# Electrical_Panel.net
KiCad netlist of a schematic drawn in Altium Designer
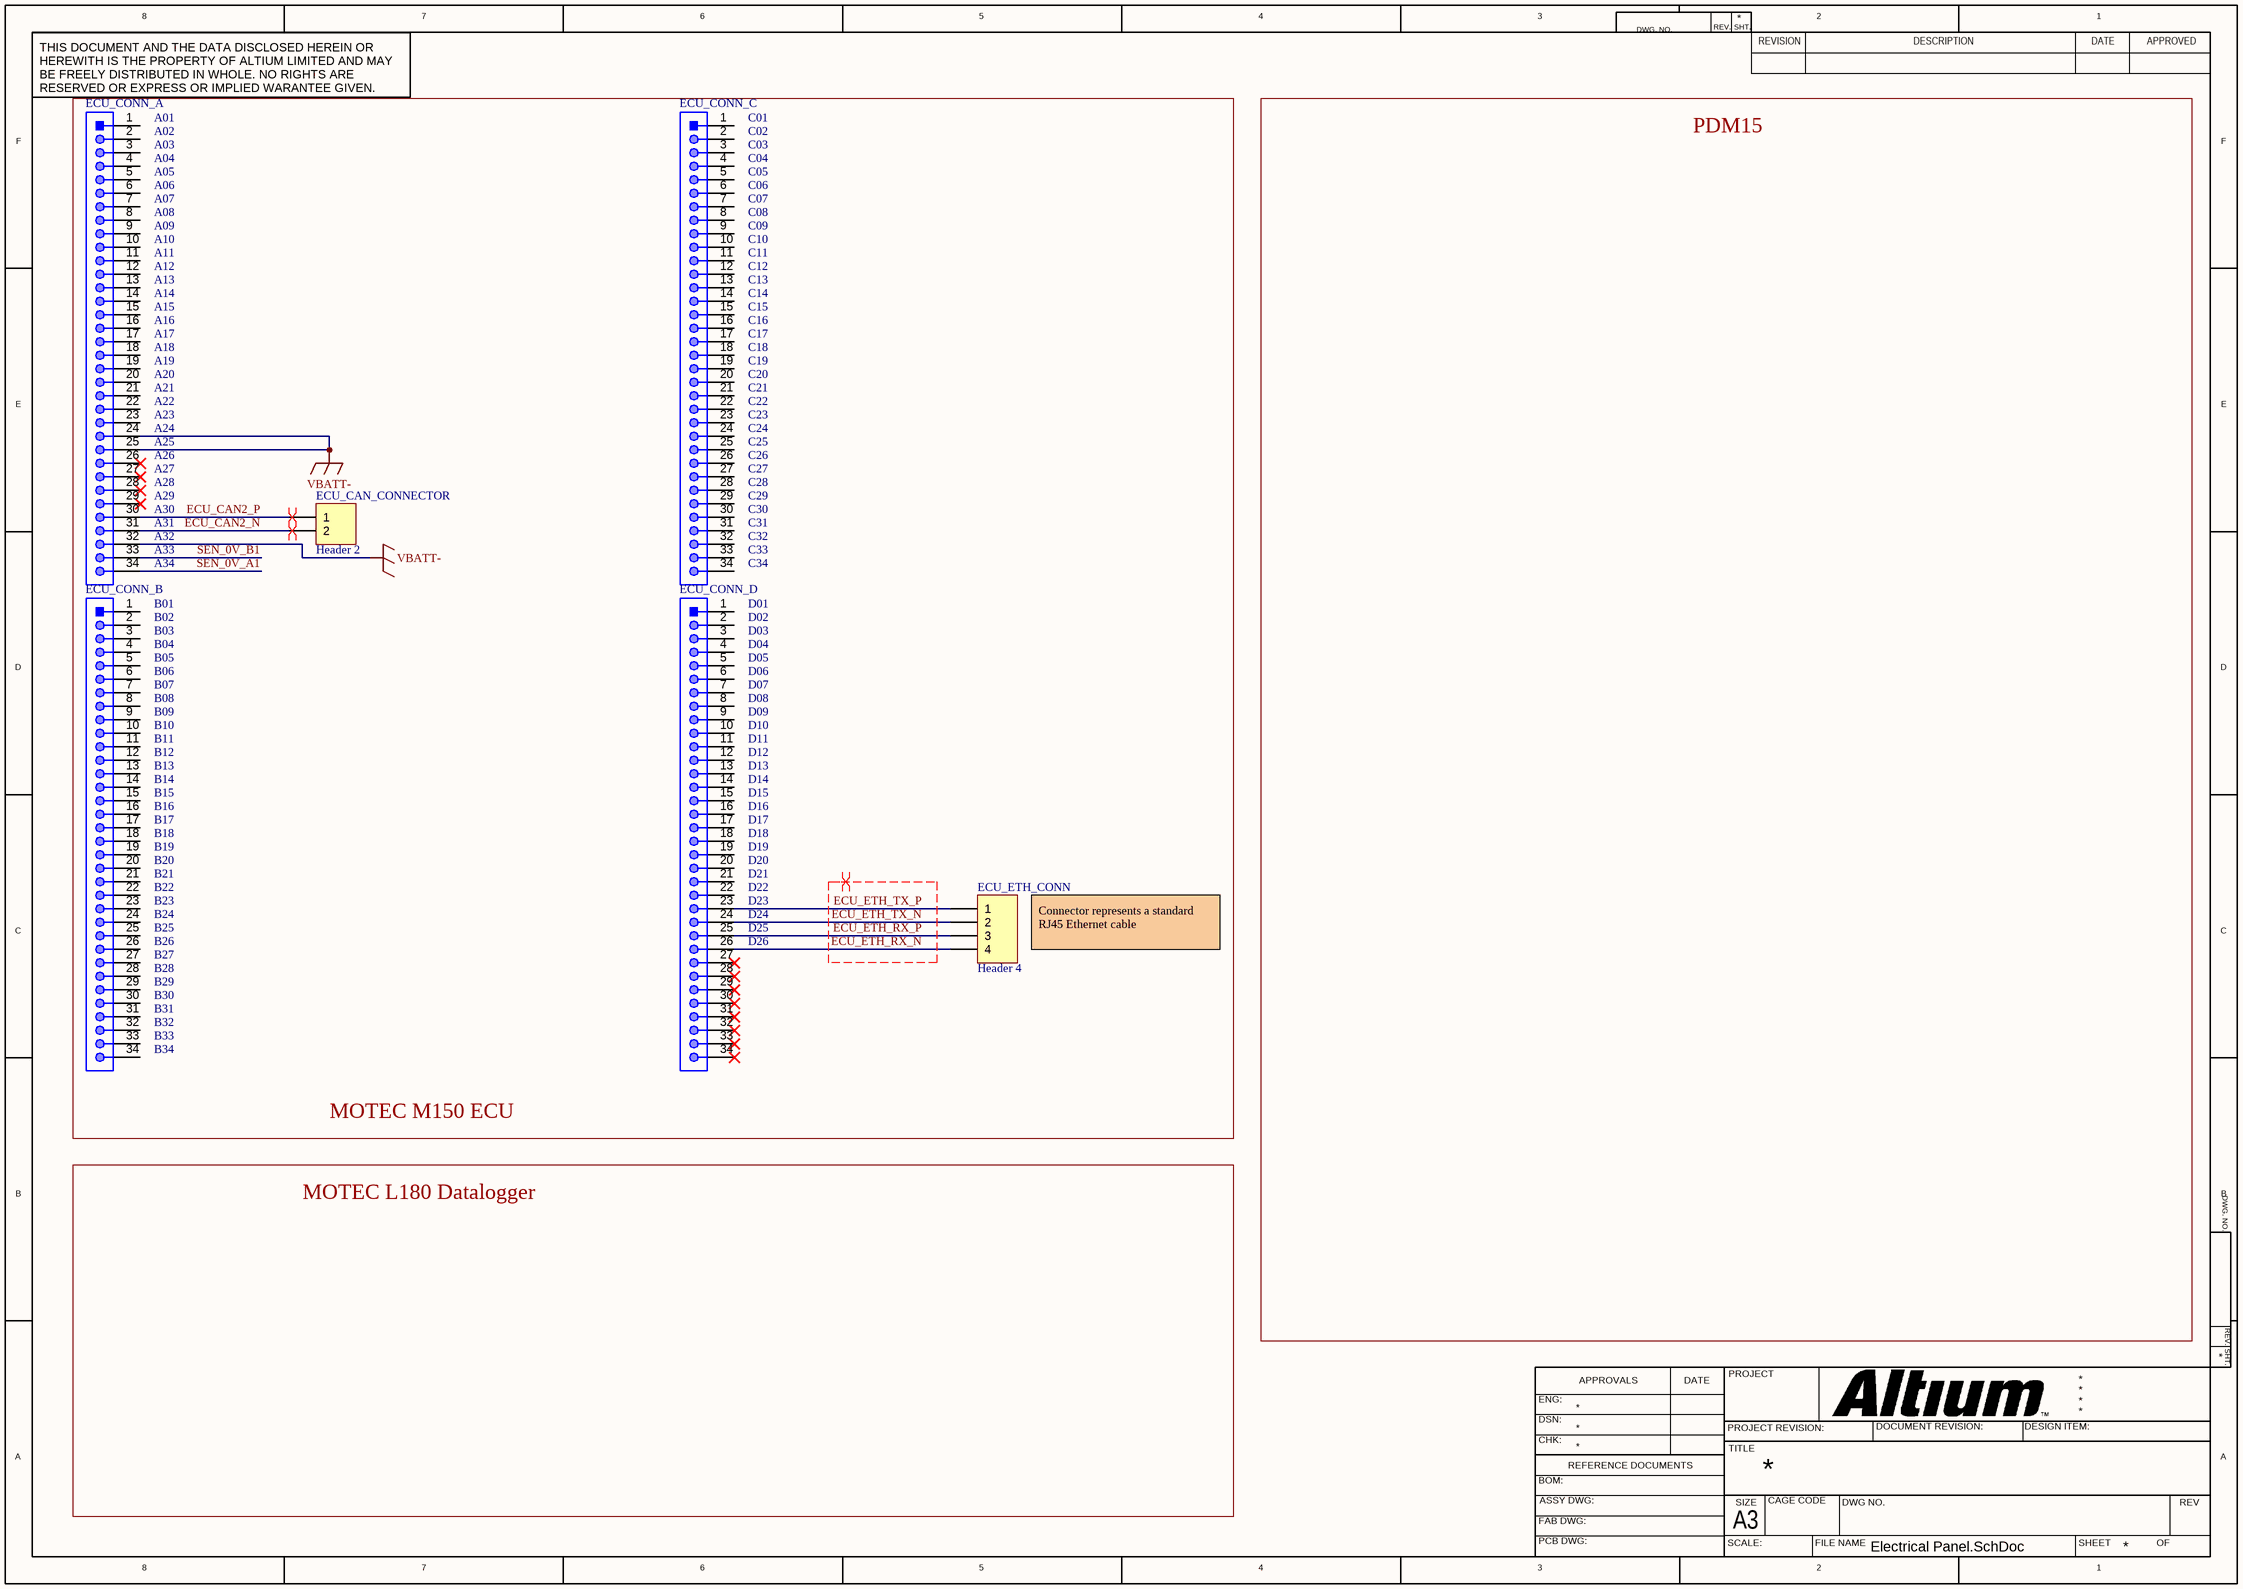
[diagram p0: Electrical Panel.SchDoc]

(export (version "E")
  (design (tool "Eeschema 10.0.6"))
  (components
    (comp (ref "ECU_CAN_CONNECTOR")
      (value "Header 2")
      (footprint "HDR1X2")
      (description "Header, 2-Pin")
      (fields (field (name "PUBLISHER") "Altium Limited"))
      (libsource (lib "Miscellaneous Connectors") (part "Header 2"))
    )
    (comp (ref "ECU_CONN_A")
      (value "61303411021")
      (footprint "61303411021")
      (description "THT Angled Pin Header WR-PHD, Pitch 2.54 mm, Single Row, 34 pins")
      (fields (field (name "MANUFACTURER") "Wurth Elektronik") (field (name "PUBLISHER") "WurthElektronik"))
      (libsource (lib "Altium Content Vault") (part "WE-CN-1P-M-R34"))
    )
    (comp (ref "ECU_CONN_B")
      (value "61303411021")
      (footprint "61303411021")
      (description "THT Angled Pin Header WR-PHD, Pitch 2.54 mm, Single Row, 34 pins")
      (fields (field (name "MANUFACTURER") "Wurth Elektronik") (field (name "PUBLISHER") "WurthElektronik"))
      (libsource (lib "Altium Content Vault") (part "WE-CN-1P-M-R34"))
    )
    (comp (ref "ECU_CONN_C")
      (value "61303411021")
      (footprint "61303411021")
      (description "THT Angled Pin Header WR-PHD, Pitch 2.54 mm, Single Row, 34 pins")
      (fields (field (name "MANUFACTURER") "Wurth Elektronik") (field (name "PUBLISHER") "WurthElektronik"))
      (libsource (lib "Altium Content Vault") (part "WE-CN-1P-M-R34"))
    )
    (comp (ref "ECU_CONN_D")
      (value "61303411021")
      (footprint "61303411021")
      (description "THT Angled Pin Header WR-PHD, Pitch 2.54 mm, Single Row, 34 pins")
      (fields (field (name "MANUFACTURER") "Wurth Elektronik") (field (name "PUBLISHER") "WurthElektronik"))
      (libsource (lib "Altium Content Vault") (part "WE-CN-1P-M-R34"))
    )
    (comp (ref "ECU_ETH_CONN")
      (value "Header 4")
      (footprint "HDR1X4")
      (description "Header, 4-Pin")
      (fields (field (name "PUBLISHER") "Altium Limited"))
      (libsource (lib "Miscellaneous Connectors") (part "Header 4"))
    )
  )
  (nets
    (net (code "1") (name "/ECU_CAN2_N") (class "Default")
      (node (ref "ECU_CAN_CONNECTOR") (pin "2") (pinfunction "2_2") (pintype "passive"))
      (node (ref "ECU_CONN_A") (pin "31") (pinfunction "31_31") (pintype "passive"))
    )
    (net (code "2") (name "/ECU_CAN2_P") (class "Default")
      (node (ref "ECU_CAN_CONNECTOR") (pin "1") (pinfunction "1_1") (pintype "passive"))
      (node (ref "ECU_CONN_A") (pin "30") (pinfunction "30_30") (pintype "passive"))
    )
    (net (code "3") (name "/ECU_ETH_RX_N") (class "Default")
      (node (ref "ECU_CONN_D") (pin "26") (pinfunction "26_26") (pintype "passive"))
      (node (ref "ECU_ETH_CONN") (pin "4") (pinfunction "4_4") (pintype "passive"))
    )
    (net (code "4") (name "/ECU_ETH_RX_P") (class "Default")
      (node (ref "ECU_CONN_D") (pin "25") (pinfunction "25_25") (pintype "passive"))
      (node (ref "ECU_ETH_CONN") (pin "3") (pinfunction "3_3") (pintype "passive"))
    )
    (net (code "5") (name "/ECU_ETH_TX_N") (class "Default")
      (node (ref "ECU_CONN_D") (pin "24") (pinfunction "24_24") (pintype "passive"))
      (node (ref "ECU_ETH_CONN") (pin "2") (pinfunction "2_2") (pintype "passive"))
    )
    (net (code "6") (name "/ECU_ETH_TX_P") (class "Default")
      (node (ref "ECU_CONN_D") (pin "23") (pinfunction "23_23") (pintype "passive"))
      (node (ref "ECU_ETH_CONN") (pin "1") (pinfunction "1_1") (pintype "passive"))
    )
    (net (code "7") (name "/SEN_0V_A1") (class "Default")
      (node (ref "ECU_CONN_A") (pin "34") (pinfunction "34_34") (pintype "passive"))
    )
    (net (code "8") (name "/SEN_0V_B1") (class "Default")
      (node (ref "ECU_CONN_A") (pin "33") (pinfunction "33_33") (pintype "passive"))
    )
    (net (code "9") (name "VBATT-") (class "Default")
      (node (ref "ECU_CONN_A") (pin "24") (pinfunction "24_24") (pintype "passive"))
      (node (ref "ECU_CONN_A") (pin "25") (pinfunction "25_25") (pintype "passive"))
      (node (ref "ECU_CONN_A") (pin "32") (pinfunction "32_32") (pintype "passive"))
    )
    (net (code "10") (name "unconnected-(ECU_CONN_A-Pad1)") (class "Default")
      (node (ref "ECU_CONN_A") (pin "1") (pinfunction "1_1") (pintype "passive"))
    )
    (net (code "11") (name "unconnected-(ECU_CONN_A-Pad2)") (class "Default")
      (node (ref "ECU_CONN_A") (pin "2") (pinfunction "2_2") (pintype "passive"))
    )
    (net (code "12") (name "unconnected-(ECU_CONN_A-Pad3)") (class "Default")
      (node (ref "ECU_CONN_A") (pin "3") (pinfunction "3_3") (pintype "passive"))
    )
    (net (code "13") (name "unconnected-(ECU_CONN_A-Pad4)") (class "Default")
      (node (ref "ECU_CONN_A") (pin "4") (pinfunction "4_4") (pintype "passive"))
    )
    (net (code "14") (name "unconnected-(ECU_CONN_A-Pad5)") (class "Default")
      (node (ref "ECU_CONN_A") (pin "5") (pinfunction "5_5") (pintype "passive"))
    )
    (net (code "15") (name "unconnected-(ECU_CONN_A-Pad6)") (class "Default")
      (node (ref "ECU_CONN_A") (pin "6") (pinfunction "6_6") (pintype "passive"))
    )
    (net (code "16") (name "unconnected-(ECU_CONN_A-Pad7)") (class "Default")
      (node (ref "ECU_CONN_A") (pin "7") (pinfunction "7_7") (pintype "passive"))
    )
    (net (code "17") (name "unconnected-(ECU_CONN_A-Pad8)") (class "Default")
      (node (ref "ECU_CONN_A") (pin "8") (pinfunction "8_8") (pintype "passive"))
    )
    (net (code "18") (name "unconnected-(ECU_CONN_A-Pad9)") (class "Default")
      (node (ref "ECU_CONN_A") (pin "9") (pinfunction "9_9") (pintype "passive"))
    )
    (net (code "19") (name "unconnected-(ECU_CONN_A-Pad10)") (class "Default")
      (node (ref "ECU_CONN_A") (pin "10") (pinfunction "10_10") (pintype "passive"))
    )
    (net (code "20") (name "unconnected-(ECU_CONN_A-Pad11)") (class "Default")
      (node (ref "ECU_CONN_A") (pin "11") (pinfunction "11_11") (pintype "passive"))
    )
    (net (code "21") (name "unconnected-(ECU_CONN_A-Pad12)") (class "Default")
      (node (ref "ECU_CONN_A") (pin "12") (pinfunction "12_12") (pintype "passive"))
    )
    (net (code "22") (name "unconnected-(ECU_CONN_A-Pad13)") (class "Default")
      (node (ref "ECU_CONN_A") (pin "13") (pinfunction "13_13") (pintype "passive"))
    )
    (net (code "23") (name "unconnected-(ECU_CONN_A-Pad14)") (class "Default")
      (node (ref "ECU_CONN_A") (pin "14") (pinfunction "14_14") (pintype "passive"))
    )
    (net (code "24") (name "unconnected-(ECU_CONN_A-Pad15)") (class "Default")
      (node (ref "ECU_CONN_A") (pin "15") (pinfunction "15_15") (pintype "passive"))
    )
    (net (code "25") (name "unconnected-(ECU_CONN_A-Pad16)") (class "Default")
      (node (ref "ECU_CONN_A") (pin "16") (pinfunction "16_16") (pintype "passive"))
    )
    (net (code "26") (name "unconnected-(ECU_CONN_A-Pad17)") (class "Default")
      (node (ref "ECU_CONN_A") (pin "17") (pinfunction "17_17") (pintype "passive"))
    )
    (net (code "27") (name "unconnected-(ECU_CONN_A-Pad18)") (class "Default")
      (node (ref "ECU_CONN_A") (pin "18") (pinfunction "18_18") (pintype "passive"))
    )
    (net (code "28") (name "unconnected-(ECU_CONN_A-Pad19)") (class "Default")
      (node (ref "ECU_CONN_A") (pin "19") (pinfunction "19_19") (pintype "passive"))
    )
    (net (code "29") (name "unconnected-(ECU_CONN_A-Pad20)") (class "Default")
      (node (ref "ECU_CONN_A") (pin "20") (pinfunction "20_20") (pintype "passive"))
    )
    (net (code "30") (name "unconnected-(ECU_CONN_A-Pad21)") (class "Default")
      (node (ref "ECU_CONN_A") (pin "21") (pinfunction "21_21") (pintype "passive"))
    )
    (net (code "31") (name "unconnected-(ECU_CONN_A-Pad22)") (class "Default")
      (node (ref "ECU_CONN_A") (pin "22") (pinfunction "22_22") (pintype "passive"))
    )
    (net (code "32") (name "unconnected-(ECU_CONN_A-Pad23)") (class "Default")
      (node (ref "ECU_CONN_A") (pin "23") (pinfunction "23_23") (pintype "passive"))
    )
    (net (code "33") (name "unconnected-(ECU_CONN_A-Pad26)") (class "Default")
      (node (ref "ECU_CONN_A") (pin "26") (pinfunction "26_26") (pintype "passive+no_connect"))
    )
    (net (code "34") (name "unconnected-(ECU_CONN_A-Pad27)") (class "Default")
      (node (ref "ECU_CONN_A") (pin "27") (pinfunction "27_27") (pintype "passive+no_connect"))
    )
    (net (code "35") (name "unconnected-(ECU_CONN_A-Pad28)") (class "Default")
      (node (ref "ECU_CONN_A") (pin "28") (pinfunction "28_28") (pintype "passive+no_connect"))
    )
    (net (code "36") (name "unconnected-(ECU_CONN_A-Pad29)") (class "Default")
      (node (ref "ECU_CONN_A") (pin "29") (pinfunction "29_29") (pintype "passive+no_connect"))
    )
    (net (code "37") (name "unconnected-(ECU_CONN_B-Pad1)") (class "Default")
      (node (ref "ECU_CONN_B") (pin "1") (pinfunction "1_1") (pintype "passive"))
    )
    (net (code "38") (name "unconnected-(ECU_CONN_B-Pad2)") (class "Default")
      (node (ref "ECU_CONN_B") (pin "2") (pinfunction "2_2") (pintype "passive"))
    )
    (net (code "39") (name "unconnected-(ECU_CONN_B-Pad3)") (class "Default")
      (node (ref "ECU_CONN_B") (pin "3") (pinfunction "3_3") (pintype "passive"))
    )
    (net (code "40") (name "unconnected-(ECU_CONN_B-Pad4)") (class "Default")
      (node (ref "ECU_CONN_B") (pin "4") (pinfunction "4_4") (pintype "passive"))
    )
    (net (code "41") (name "unconnected-(ECU_CONN_B-Pad5)") (class "Default")
      (node (ref "ECU_CONN_B") (pin "5") (pinfunction "5_5") (pintype "passive"))
    )
    (net (code "42") (name "unconnected-(ECU_CONN_B-Pad6)") (class "Default")
      (node (ref "ECU_CONN_B") (pin "6") (pinfunction "6_6") (pintype "passive"))
    )
    (net (code "43") (name "unconnected-(ECU_CONN_B-Pad7)") (class "Default")
      (node (ref "ECU_CONN_B") (pin "7") (pinfunction "7_7") (pintype "passive"))
    )
    (net (code "44") (name "unconnected-(ECU_CONN_B-Pad8)") (class "Default")
      (node (ref "ECU_CONN_B") (pin "8") (pinfunction "8_8") (pintype "passive"))
    )
    (net (code "45") (name "unconnected-(ECU_CONN_B-Pad9)") (class "Default")
      (node (ref "ECU_CONN_B") (pin "9") (pinfunction "9_9") (pintype "passive"))
    )
    (net (code "46") (name "unconnected-(ECU_CONN_B-Pad10)") (class "Default")
      (node (ref "ECU_CONN_B") (pin "10") (pinfunction "10_10") (pintype "passive"))
    )
    (net (code "47") (name "unconnected-(ECU_CONN_B-Pad11)") (class "Default")
      (node (ref "ECU_CONN_B") (pin "11") (pinfunction "11_11") (pintype "passive"))
    )
    (net (code "48") (name "unconnected-(ECU_CONN_B-Pad12)") (class "Default")
      (node (ref "ECU_CONN_B") (pin "12") (pinfunction "12_12") (pintype "passive"))
    )
    (net (code "49") (name "unconnected-(ECU_CONN_B-Pad13)") (class "Default")
      (node (ref "ECU_CONN_B") (pin "13") (pinfunction "13_13") (pintype "passive"))
    )
    (net (code "50") (name "unconnected-(ECU_CONN_B-Pad14)") (class "Default")
      (node (ref "ECU_CONN_B") (pin "14") (pinfunction "14_14") (pintype "passive"))
    )
    (net (code "51") (name "unconnected-(ECU_CONN_B-Pad15)") (class "Default")
      (node (ref "ECU_CONN_B") (pin "15") (pinfunction "15_15") (pintype "passive"))
    )
    (net (code "52") (name "unconnected-(ECU_CONN_B-Pad16)") (class "Default")
      (node (ref "ECU_CONN_B") (pin "16") (pinfunction "16_16") (pintype "passive"))
    )
    (net (code "53") (name "unconnected-(ECU_CONN_B-Pad17)") (class "Default")
      (node (ref "ECU_CONN_B") (pin "17") (pinfunction "17_17") (pintype "passive"))
    )
    (net (code "54") (name "unconnected-(ECU_CONN_B-Pad18)") (class "Default")
      (node (ref "ECU_CONN_B") (pin "18") (pinfunction "18_18") (pintype "passive"))
    )
    (net (code "55") (name "unconnected-(ECU_CONN_B-Pad19)") (class "Default")
      (node (ref "ECU_CONN_B") (pin "19") (pinfunction "19_19") (pintype "passive"))
    )
    (net (code "56") (name "unconnected-(ECU_CONN_B-Pad20)") (class "Default")
      (node (ref "ECU_CONN_B") (pin "20") (pinfunction "20_20") (pintype "passive"))
    )
    (net (code "57") (name "unconnected-(ECU_CONN_B-Pad21)") (class "Default")
      (node (ref "ECU_CONN_B") (pin "21") (pinfunction "21_21") (pintype "passive"))
    )
    (net (code "58") (name "unconnected-(ECU_CONN_B-Pad22)") (class "Default")
      (node (ref "ECU_CONN_B") (pin "22") (pinfunction "22_22") (pintype "passive"))
    )
    (net (code "59") (name "unconnected-(ECU_CONN_B-Pad23)") (class "Default")
      (node (ref "ECU_CONN_B") (pin "23") (pinfunction "23_23") (pintype "passive"))
    )
    (net (code "60") (name "unconnected-(ECU_CONN_B-Pad24)") (class "Default")
      (node (ref "ECU_CONN_B") (pin "24") (pinfunction "24_24") (pintype "passive"))
    )
    (net (code "61") (name "unconnected-(ECU_CONN_B-Pad25)") (class "Default")
      (node (ref "ECU_CONN_B") (pin "25") (pinfunction "25_25") (pintype "passive"))
    )
    (net (code "62") (name "unconnected-(ECU_CONN_B-Pad26)") (class "Default")
      (node (ref "ECU_CONN_B") (pin "26") (pinfunction "26_26") (pintype "passive"))
    )
    (net (code "63") (name "unconnected-(ECU_CONN_B-Pad27)") (class "Default")
      (node (ref "ECU_CONN_B") (pin "27") (pinfunction "27_27") (pintype "passive"))
    )
    (net (code "64") (name "unconnected-(ECU_CONN_B-Pad28)") (class "Default")
      (node (ref "ECU_CONN_B") (pin "28") (pinfunction "28_28") (pintype "passive"))
    )
    (net (code "65") (name "unconnected-(ECU_CONN_B-Pad29)") (class "Default")
      (node (ref "ECU_CONN_B") (pin "29") (pinfunction "29_29") (pintype "passive"))
    )
    (net (code "66") (name "unconnected-(ECU_CONN_B-Pad30)") (class "Default")
      (node (ref "ECU_CONN_B") (pin "30") (pinfunction "30_30") (pintype "passive"))
    )
    (net (code "67") (name "unconnected-(ECU_CONN_B-Pad31)") (class "Default")
      (node (ref "ECU_CONN_B") (pin "31") (pinfunction "31_31") (pintype "passive"))
    )
    (net (code "68") (name "unconnected-(ECU_CONN_B-Pad32)") (class "Default")
      (node (ref "ECU_CONN_B") (pin "32") (pinfunction "32_32") (pintype "passive"))
    )
    (net (code "69") (name "unconnected-(ECU_CONN_B-Pad33)") (class "Default")
      (node (ref "ECU_CONN_B") (pin "33") (pinfunction "33_33") (pintype "passive"))
    )
    (net (code "70") (name "unconnected-(ECU_CONN_B-Pad34)") (class "Default")
      (node (ref "ECU_CONN_B") (pin "34") (pinfunction "34_34") (pintype "passive"))
    )
    (net (code "71") (name "unconnected-(ECU_CONN_C-Pad1)") (class "Default")
      (node (ref "ECU_CONN_C") (pin "1") (pinfunction "1_1") (pintype "passive"))
    )
    (net (code "72") (name "unconnected-(ECU_CONN_C-Pad2)") (class "Default")
      (node (ref "ECU_CONN_C") (pin "2") (pinfunction "2_2") (pintype "passive"))
    )
    (net (code "73") (name "unconnected-(ECU_CONN_C-Pad3)") (class "Default")
      (node (ref "ECU_CONN_C") (pin "3") (pinfunction "3_3") (pintype "passive"))
    )
    (net (code "74") (name "unconnected-(ECU_CONN_C-Pad4)") (class "Default")
      (node (ref "ECU_CONN_C") (pin "4") (pinfunction "4_4") (pintype "passive"))
    )
    (net (code "75") (name "unconnected-(ECU_CONN_C-Pad5)") (class "Default")
      (node (ref "ECU_CONN_C") (pin "5") (pinfunction "5_5") (pintype "passive"))
    )
    (net (code "76") (name "unconnected-(ECU_CONN_C-Pad6)") (class "Default")
      (node (ref "ECU_CONN_C") (pin "6") (pinfunction "6_6") (pintype "passive"))
    )
    (net (code "77") (name "unconnected-(ECU_CONN_C-Pad7)") (class "Default")
      (node (ref "ECU_CONN_C") (pin "7") (pinfunction "7_7") (pintype "passive"))
    )
    (net (code "78") (name "unconnected-(ECU_CONN_C-Pad8)") (class "Default")
      (node (ref "ECU_CONN_C") (pin "8") (pinfunction "8_8") (pintype "passive"))
    )
    (net (code "79") (name "unconnected-(ECU_CONN_C-Pad9)") (class "Default")
      (node (ref "ECU_CONN_C") (pin "9") (pinfunction "9_9") (pintype "passive"))
    )
    (net (code "80") (name "unconnected-(ECU_CONN_C-Pad10)") (class "Default")
      (node (ref "ECU_CONN_C") (pin "10") (pinfunction "10_10") (pintype "passive"))
    )
    (net (code "81") (name "unconnected-(ECU_CONN_C-Pad11)") (class "Default")
      (node (ref "ECU_CONN_C") (pin "11") (pinfunction "11_11") (pintype "passive"))
    )
    (net (code "82") (name "unconnected-(ECU_CONN_C-Pad12)") (class "Default")
      (node (ref "ECU_CONN_C") (pin "12") (pinfunction "12_12") (pintype "passive"))
    )
    (net (code "83") (name "unconnected-(ECU_CONN_C-Pad13)") (class "Default")
      (node (ref "ECU_CONN_C") (pin "13") (pinfunction "13_13") (pintype "passive"))
    )
    (net (code "84") (name "unconnected-(ECU_CONN_C-Pad14)") (class "Default")
      (node (ref "ECU_CONN_C") (pin "14") (pinfunction "14_14") (pintype "passive"))
    )
    (net (code "85") (name "unconnected-(ECU_CONN_C-Pad15)") (class "Default")
      (node (ref "ECU_CONN_C") (pin "15") (pinfunction "15_15") (pintype "passive"))
    )
    (net (code "86") (name "unconnected-(ECU_CONN_C-Pad16)") (class "Default")
      (node (ref "ECU_CONN_C") (pin "16") (pinfunction "16_16") (pintype "passive"))
    )
    (net (code "87") (name "unconnected-(ECU_CONN_C-Pad17)") (class "Default")
      (node (ref "ECU_CONN_C") (pin "17") (pinfunction "17_17") (pintype "passive"))
    )
    (net (code "88") (name "unconnected-(ECU_CONN_C-Pad18)") (class "Default")
      (node (ref "ECU_CONN_C") (pin "18") (pinfunction "18_18") (pintype "passive"))
    )
    (net (code "89") (name "unconnected-(ECU_CONN_C-Pad19)") (class "Default")
      (node (ref "ECU_CONN_C") (pin "19") (pinfunction "19_19") (pintype "passive"))
    )
    (net (code "90") (name "unconnected-(ECU_CONN_C-Pad20)") (class "Default")
      (node (ref "ECU_CONN_C") (pin "20") (pinfunction "20_20") (pintype "passive"))
    )
    (net (code "91") (name "unconnected-(ECU_CONN_C-Pad21)") (class "Default")
      (node (ref "ECU_CONN_C") (pin "21") (pinfunction "21_21") (pintype "passive"))
    )
    (net (code "92") (name "unconnected-(ECU_CONN_C-Pad22)") (class "Default")
      (node (ref "ECU_CONN_C") (pin "22") (pinfunction "22_22") (pintype "passive"))
    )
    (net (code "93") (name "unconnected-(ECU_CONN_C-Pad23)") (class "Default")
      (node (ref "ECU_CONN_C") (pin "23") (pinfunction "23_23") (pintype "passive"))
    )
    (net (code "94") (name "unconnected-(ECU_CONN_C-Pad24)") (class "Default")
      (node (ref "ECU_CONN_C") (pin "24") (pinfunction "24_24") (pintype "passive"))
    )
    (net (code "95") (name "unconnected-(ECU_CONN_C-Pad25)") (class "Default")
      (node (ref "ECU_CONN_C") (pin "25") (pinfunction "25_25") (pintype "passive"))
    )
    (net (code "96") (name "unconnected-(ECU_CONN_C-Pad26)") (class "Default")
      (node (ref "ECU_CONN_C") (pin "26") (pinfunction "26_26") (pintype "passive"))
    )
    (net (code "97") (name "unconnected-(ECU_CONN_C-Pad27)") (class "Default")
      (node (ref "ECU_CONN_C") (pin "27") (pinfunction "27_27") (pintype "passive"))
    )
    (net (code "98") (name "unconnected-(ECU_CONN_C-Pad28)") (class "Default")
      (node (ref "ECU_CONN_C") (pin "28") (pinfunction "28_28") (pintype "passive"))
    )
    (net (code "99") (name "unconnected-(ECU_CONN_C-Pad29)") (class "Default")
      (node (ref "ECU_CONN_C") (pin "29") (pinfunction "29_29") (pintype "passive"))
    )
    (net (code "100") (name "unconnected-(ECU_CONN_C-Pad30)") (class "Default")
      (node (ref "ECU_CONN_C") (pin "30") (pinfunction "30_30") (pintype "passive"))
    )
    (net (code "101") (name "unconnected-(ECU_CONN_C-Pad31)") (class "Default")
      (node (ref "ECU_CONN_C") (pin "31") (pinfunction "31_31") (pintype "passive"))
    )
    (net (code "102") (name "unconnected-(ECU_CONN_C-Pad32)") (class "Default")
      (node (ref "ECU_CONN_C") (pin "32") (pinfunction "32_32") (pintype "passive"))
    )
    (net (code "103") (name "unconnected-(ECU_CONN_C-Pad33)") (class "Default")
      (node (ref "ECU_CONN_C") (pin "33") (pinfunction "33_33") (pintype "passive"))
    )
    (net (code "104") (name "unconnected-(ECU_CONN_C-Pad34)") (class "Default")
      (node (ref "ECU_CONN_C") (pin "34") (pinfunction "34_34") (pintype "passive"))
    )
    (net (code "105") (name "unconnected-(ECU_CONN_D-Pad1)") (class "Default")
      (node (ref "ECU_CONN_D") (pin "1") (pinfunction "1_1") (pintype "passive"))
    )
    (net (code "106") (name "unconnected-(ECU_CONN_D-Pad2)") (class "Default")
      (node (ref "ECU_CONN_D") (pin "2") (pinfunction "2_2") (pintype "passive"))
    )
    (net (code "107") (name "unconnected-(ECU_CONN_D-Pad3)") (class "Default")
      (node (ref "ECU_CONN_D") (pin "3") (pinfunction "3_3") (pintype "passive"))
    )
    (net (code "108") (name "unconnected-(ECU_CONN_D-Pad4)") (class "Default")
      (node (ref "ECU_CONN_D") (pin "4") (pinfunction "4_4") (pintype "passive"))
    )
    (net (code "109") (name "unconnected-(ECU_CONN_D-Pad5)") (class "Default")
      (node (ref "ECU_CONN_D") (pin "5") (pinfunction "5_5") (pintype "passive"))
    )
    (net (code "110") (name "unconnected-(ECU_CONN_D-Pad6)") (class "Default")
      (node (ref "ECU_CONN_D") (pin "6") (pinfunction "6_6") (pintype "passive"))
    )
    (net (code "111") (name "unconnected-(ECU_CONN_D-Pad7)") (class "Default")
      (node (ref "ECU_CONN_D") (pin "7") (pinfunction "7_7") (pintype "passive"))
    )
    (net (code "112") (name "unconnected-(ECU_CONN_D-Pad8)") (class "Default")
      (node (ref "ECU_CONN_D") (pin "8") (pinfunction "8_8") (pintype "passive"))
    )
    (net (code "113") (name "unconnected-(ECU_CONN_D-Pad9)") (class "Default")
      (node (ref "ECU_CONN_D") (pin "9") (pinfunction "9_9") (pintype "passive"))
    )
    (net (code "114") (name "unconnected-(ECU_CONN_D-Pad10)") (class "Default")
      (node (ref "ECU_CONN_D") (pin "10") (pinfunction "10_10") (pintype "passive"))
    )
    (net (code "115") (name "unconnected-(ECU_CONN_D-Pad11)") (class "Default")
      (node (ref "ECU_CONN_D") (pin "11") (pinfunction "11_11") (pintype "passive"))
    )
    (net (code "116") (name "unconnected-(ECU_CONN_D-Pad12)") (class "Default")
      (node (ref "ECU_CONN_D") (pin "12") (pinfunction "12_12") (pintype "passive"))
    )
    (net (code "117") (name "unconnected-(ECU_CONN_D-Pad13)") (class "Default")
      (node (ref "ECU_CONN_D") (pin "13") (pinfunction "13_13") (pintype "passive"))
    )
    (net (code "118") (name "unconnected-(ECU_CONN_D-Pad14)") (class "Default")
      (node (ref "ECU_CONN_D") (pin "14") (pinfunction "14_14") (pintype "passive"))
    )
    (net (code "119") (name "unconnected-(ECU_CONN_D-Pad15)") (class "Default")
      (node (ref "ECU_CONN_D") (pin "15") (pinfunction "15_15") (pintype "passive"))
    )
    (net (code "120") (name "unconnected-(ECU_CONN_D-Pad16)") (class "Default")
      (node (ref "ECU_CONN_D") (pin "16") (pinfunction "16_16") (pintype "passive"))
    )
    (net (code "121") (name "unconnected-(ECU_CONN_D-Pad17)") (class "Default")
      (node (ref "ECU_CONN_D") (pin "17") (pinfunction "17_17") (pintype "passive"))
    )
    (net (code "122") (name "unconnected-(ECU_CONN_D-Pad18)") (class "Default")
      (node (ref "ECU_CONN_D") (pin "18") (pinfunction "18_18") (pintype "passive"))
    )
    (net (code "123") (name "unconnected-(ECU_CONN_D-Pad19)") (class "Default")
      (node (ref "ECU_CONN_D") (pin "19") (pinfunction "19_19") (pintype "passive"))
    )
    (net (code "124") (name "unconnected-(ECU_CONN_D-Pad20)") (class "Default")
      (node (ref "ECU_CONN_D") (pin "20") (pinfunction "20_20") (pintype "passive"))
    )
    (net (code "125") (name "unconnected-(ECU_CONN_D-Pad21)") (class "Default")
      (node (ref "ECU_CONN_D") (pin "21") (pinfunction "21_21") (pintype "passive"))
    )
    (net (code "126") (name "unconnected-(ECU_CONN_D-Pad22)") (class "Default")
      (node (ref "ECU_CONN_D") (pin "22") (pinfunction "22_22") (pintype "passive"))
    )
    (net (code "127") (name "unconnected-(ECU_CONN_D-Pad27)") (class "Default")
      (node (ref "ECU_CONN_D") (pin "27") (pinfunction "27_27") (pintype "passive+no_connect"))
    )
    (net (code "128") (name "unconnected-(ECU_CONN_D-Pad28)") (class "Default")
      (node (ref "ECU_CONN_D") (pin "28") (pinfunction "28_28") (pintype "passive+no_connect"))
    )
    (net (code "129") (name "unconnected-(ECU_CONN_D-Pad29)") (class "Default")
      (node (ref "ECU_CONN_D") (pin "29") (pinfunction "29_29") (pintype "passive+no_connect"))
    )
    (net (code "130") (name "unconnected-(ECU_CONN_D-Pad30)") (class "Default")
      (node (ref "ECU_CONN_D") (pin "30") (pinfunction "30_30") (pintype "passive+no_connect"))
    )
    (net (code "131") (name "unconnected-(ECU_CONN_D-Pad31)") (class "Default")
      (node (ref "ECU_CONN_D") (pin "31") (pinfunction "31_31") (pintype "passive+no_connect"))
    )
    (net (code "132") (name "unconnected-(ECU_CONN_D-Pad32)") (class "Default")
      (node (ref "ECU_CONN_D") (pin "32") (pinfunction "32_32") (pintype "passive+no_connect"))
    )
    (net (code "133") (name "unconnected-(ECU_CONN_D-Pad33)") (class "Default")
      (node (ref "ECU_CONN_D") (pin "33") (pinfunction "33_33") (pintype "passive+no_connect"))
    )
    (net (code "134") (name "unconnected-(ECU_CONN_D-Pad34)") (class "Default")
      (node (ref "ECU_CONN_D") (pin "34") (pinfunction "34_34") (pintype "passive+no_connect"))
    )
  )
)
